# 2017_LEVI.net
KiCad netlist of a schematic drawn in Altium Designer
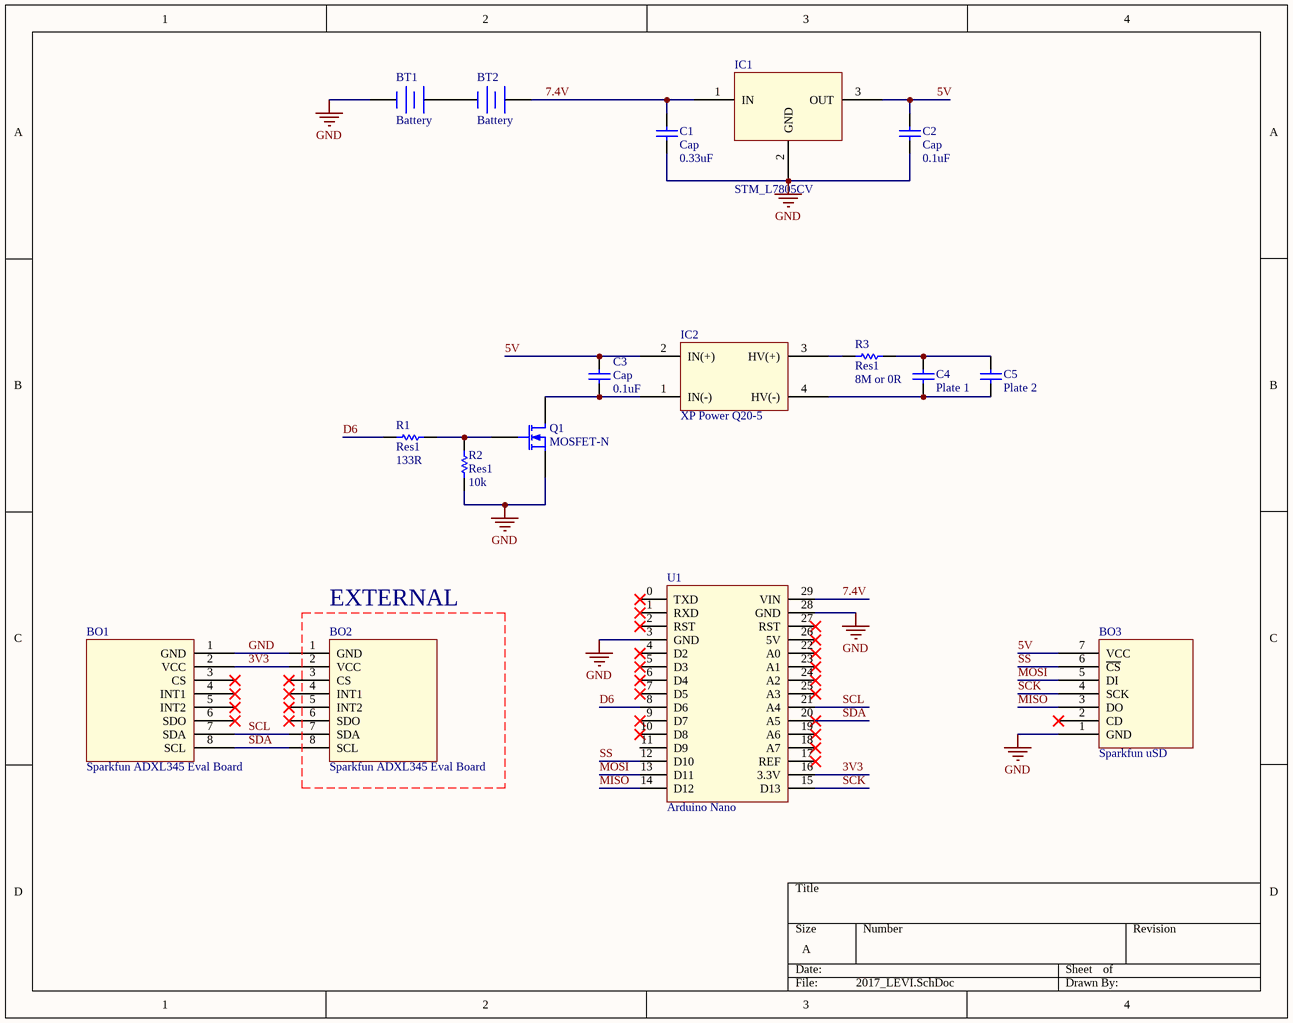
[diagram p0: 2017_LEVI.SchDoc]

(export (version "E")
  (design (tool "Eeschema 10.0.6"))
  (components
    (comp (ref "BO1")
      (value "Sparkfun ADXL345 Eval Board")
      (footprint "Sparkfun ADXL345 Breakout")
      (libsource (lib "") (part "Sparkfun ADXL345 Eval Board_1"))
    )
    (comp (ref "BO2")
      (value "Sparkfun ADXL345 Eval Board")
      (footprint "Sparkfun ADXL345 Breakout")
      (libsource (lib "2017_LEVI") (part "Sparkfun ADXL345 Eval Board"))
    )
    (comp (ref "BO3")
      (value "Sparkfun uSD")
      (footprint "Sparkfun MicroSD Breakout")
      (libsource (lib "2017_LEVI") (part "Sparkfun uSD"))
    )
    (comp (ref "BT1")
      (value "Battery")
      (footprint "BAT-2")
      (description "Multicell Battery")
      (fields (field (name "PUBLISHER") "Altium Limited"))
      (libsource (lib "Miscellaneous Devices") (part "Battery"))
    )
    (comp (ref "BT2")
      (value "Battery")
      (footprint "BAT-2")
      (description "Multicell Battery")
      (fields (field (name "PUBLISHER") "Altium Limited"))
      (libsource (lib "Miscellaneous Devices") (part "Battery"))
    )
    (comp (ref "C1")
      (value "Cap")
      (footprint "RAD-0.3")
      (description "Capacitor")
      (fields (field (name "ALTIUM_VALUE") "0.33uF") (field (name "PUBLISHER") "Altium Limited"))
      (libsource (lib "Miscellaneous Devices") (part "Cap"))
    )
    (comp (ref "C2")
      (value "Cap")
      (footprint "RAD-0.3")
      (description "Capacitor")
      (fields (field (name "ALTIUM_VALUE") "0.1uF") (field (name "PUBLISHER") "Altium Limited"))
      (libsource (lib "Miscellaneous Devices") (part "Cap"))
    )
    (comp (ref "C3")
      (value "Cap")
      (footprint "RAD-0.3")
      (description "Capacitor")
      (fields (field (name "ALTIUM_VALUE") "0.1uF") (field (name "PUBLISHER") "Altium Limited"))
      (libsource (lib "Miscellaneous Devices") (part "Cap"))
    )
    (comp (ref "C4")
      (value "Plate 1")
      (footprint "RAD-0.3")
      (description "Capacitor")
      (fields (field (name "PUBLISHER") "Altium Limited"))
      (libsource (lib "Miscellaneous Devices") (part "Cap"))
    )
    (comp (ref "C5")
      (value "Plate 2")
      (footprint "RAD-0.3")
      (description "Capacitor")
      (fields (field (name "PUBLISHER") "Altium Limited"))
      (libsource (lib "Miscellaneous Devices") (part "Cap"))
    )
    (comp (ref "IC1") (value "STM_L7805CV") (libsource (lib "2017_LEVI") (part "STM_L7805CV")))
    (comp (ref "IC2") (value "XP Power Q20-5") (libsource (lib "2017_LEVI") (part "XP Power Q20-5")))
    (comp (ref "Q1")
      (value "MOSFET-N")
      (footprint "E3")
      (description "N-Channel MOSFET")
      (fields (field (name "PUBLISHER") "Altium Limited"))
      (libsource (lib "Miscellaneous Devices") (part "MOSFET-N"))
    )
    (comp (ref "R1")
      (value "Res1")
      (footprint "AXIAL-0.3")
      (description "Resistor")
      (fields (field (name "ALTIUM_VALUE") "133R") (field (name "PUBLISHER") "Altium Limited"))
      (libsource (lib "Miscellaneous Devices") (part "Res1"))
    )
    (comp (ref "R2")
      (value "Res1")
      (footprint "AXIAL-0.3")
      (description "Resistor")
      (fields (field (name "ALTIUM_VALUE") "10k") (field (name "PUBLISHER") "Altium Limited"))
      (libsource (lib "Miscellaneous Devices") (part "Res1"))
    )
    (comp (ref "R3")
      (value "Res1")
      (footprint "AXIAL-0.3")
      (description "Resistor")
      (fields (field (name "ALTIUM_VALUE") "8M or 0R") (field (name "PUBLISHER") "Altium Limited"))
      (libsource (lib "Miscellaneous Devices") (part "Res1"))
    )
    (comp (ref "U1")
      (value "Arduino Nano")
      (footprint "Arduino Nano")
      (libsource (lib "2017_LEVI") (part "Arduino Nano"))
    )
  )
  (nets
    (net (code "1") (name "/3V3") (class "Default")
      (node (ref "BO1") (pin "2") (pinfunction "VCC_2") (pintype "passive"))
      (node (ref "BO2") (pin "2") (pinfunction "VCC_2") (pintype "passive"))
      (node (ref "U1") (pin "16") (pinfunction "3.3V_16") (pintype "passive"))
    )
    (net (code "2") (name "/5V") (class "Default")
      (node (ref "BO3") (pin "7") (pinfunction "VCC_7") (pintype "passive"))
      (node (ref "C2") (pin "2") (pinfunction "2_2") (pintype "passive"))
      (node (ref "C3") (pin "2") (pinfunction "2_2") (pintype "passive"))
      (node (ref "IC1") (pin "3") (pinfunction "OUT_3") (pintype "passive"))
      (node (ref "IC2") (pin "2") (pinfunction "IN(+)_2") (pintype "passive"))
    )
    (net (code "3") (name "/7.4V") (class "Default")
      (node (ref "BT2") (pin "1") (pinfunction "+_1") (pintype "passive"))
      (node (ref "C1") (pin "2") (pinfunction "2_2") (pintype "passive"))
      (node (ref "IC1") (pin "1") (pinfunction "IN_1") (pintype "passive"))
      (node (ref "U1") (pin "29") (pinfunction "VIN_29") (pintype "passive"))
    )
    (net (code "4") (name "/D6") (class "Default")
      (node (ref "R1") (pin "1") (pinfunction "1_1") (pintype "passive"))
      (node (ref "U1") (pin "8") (pinfunction "D6_8") (pintype "passive"))
    )
    (net (code "5") (name "/MISO") (class "Default")
      (node (ref "BO3") (pin "3") (pinfunction "DO_3") (pintype "passive"))
      (node (ref "U1") (pin "14") (pinfunction "D12_14") (pintype "passive"))
    )
    (net (code "6") (name "/MOSI") (class "Default")
      (node (ref "BO3") (pin "5") (pinfunction "DI_5") (pintype "passive"))
      (node (ref "U1") (pin "13") (pinfunction "D11_13") (pintype "passive"))
    )
    (net (code "7") (name "/SCK") (class "Default")
      (node (ref "BO3") (pin "4") (pinfunction "SCK_4") (pintype "passive"))
      (node (ref "U1") (pin "15") (pinfunction "D13_15") (pintype "passive"))
    )
    (net (code "8") (name "/SCL") (class "Default")
      (node (ref "BO1") (pin "7") (pinfunction "SDA_7") (pintype "passive"))
      (node (ref "BO2") (pin "7") (pinfunction "SDA_7") (pintype "passive"))
      (node (ref "U1") (pin "21") (pinfunction "A4_21") (pintype "passive"))
    )
    (net (code "9") (name "/SDA") (class "Default")
      (node (ref "BO1") (pin "8") (pinfunction "SCL_8") (pintype "passive"))
      (node (ref "BO2") (pin "8") (pinfunction "SCL_8") (pintype "passive"))
      (node (ref "U1") (pin "20") (pinfunction "A5_20") (pintype "passive"))
    )
    (net (code "10") (name "/SS") (class "Default")
      (node (ref "BO3") (pin "6") (pinfunction "~{CS}_6") (pintype "passive"))
      (node (ref "U1") (pin "12") (pinfunction "D10_12") (pintype "passive"))
    )
    (net (code "11") (name "GND") (class "Default")
      (node (ref "BO1") (pin "1") (pinfunction "GND_1") (pintype "passive"))
      (node (ref "BO2") (pin "1") (pinfunction "GND_1") (pintype "passive"))
      (node (ref "BO3") (pin "1") (pinfunction "GND_1") (pintype "passive"))
      (node (ref "BT1") (pin "2") (pinfunction "-_2") (pintype "passive"))
      (node (ref "C1") (pin "1") (pinfunction "1_1") (pintype "passive"))
      (node (ref "C2") (pin "1") (pinfunction "1_1") (pintype "passive"))
      (node (ref "IC1") (pin "2") (pinfunction "GND_2") (pintype "passive"))
      (node (ref "Q1") (pin "3") (pinfunction "S_3") (pintype "passive"))
      (node (ref "R2") (pin "1") (pinfunction "1_1") (pintype "passive"))
      (node (ref "U1") (pin "28") (pinfunction "GND_28") (pintype "passive"))
      (node (ref "U1") (pin "3") (pinfunction "GND_3") (pintype "passive"))
    )
    (net (code "12") (name "Net-(BT1-+)") (class "Default")
      (node (ref "BT1") (pin "1") (pinfunction "+_1") (pintype "passive"))
      (node (ref "BT2") (pin "2") (pinfunction "-_2") (pintype "passive"))
    )
    (net (code "13") (name "Net-(C4-Pad2)") (class "Default")
      (node (ref "C4") (pin "2") (pinfunction "2_2") (pintype "passive"))
      (node (ref "C5") (pin "2") (pinfunction "2_2") (pintype "passive"))
      (node (ref "R3") (pin "2") (pinfunction "2_2") (pintype "passive"))
    )
    (net (code "14") (name "Net-(IC2-HV(+))") (class "Default")
      (node (ref "IC2") (pin "3") (pinfunction "HV(+)_3") (pintype "passive"))
      (node (ref "R3") (pin "1") (pinfunction "1_1") (pintype "passive"))
    )
    (net (code "15") (name "Net-(IC2-HV(-))") (class "Default")
      (node (ref "C4") (pin "1") (pinfunction "1_1") (pintype "passive"))
      (node (ref "C5") (pin "1") (pinfunction "1_1") (pintype "passive"))
      (node (ref "IC2") (pin "4") (pinfunction "HV(-)_4") (pintype "passive"))
    )
    (net (code "16") (name "Net-(IC2-IN(-))") (class "Default")
      (node (ref "C3") (pin "1") (pinfunction "1_1") (pintype "passive"))
      (node (ref "IC2") (pin "1") (pinfunction "IN(-)_1") (pintype "passive"))
      (node (ref "Q1") (pin "2") (pinfunction "D_2") (pintype "passive"))
    )
    (net (code "17") (name "Net-(Q1-G)") (class "Default")
      (node (ref "Q1") (pin "1") (pinfunction "G_1") (pintype "passive"))
      (node (ref "R1") (pin "2") (pinfunction "2_2") (pintype "passive"))
      (node (ref "R2") (pin "2") (pinfunction "2_2") (pintype "passive"))
    )
    (net (code "18") (name "unconnected-(BO1-CS-Pad3)") (class "Default")
      (node (ref "BO1") (pin "3") (pinfunction "CS_3") (pintype "passive+no_connect"))
    )
    (net (code "19") (name "unconnected-(BO1-INT1-Pad4)") (class "Default")
      (node (ref "BO1") (pin "4") (pinfunction "INT1_4") (pintype "passive+no_connect"))
    )
    (net (code "20") (name "unconnected-(BO1-INT2-Pad5)") (class "Default")
      (node (ref "BO1") (pin "5") (pinfunction "INT2_5") (pintype "passive+no_connect"))
    )
    (net (code "21") (name "unconnected-(BO1-SDO-Pad6)") (class "Default")
      (node (ref "BO1") (pin "6") (pinfunction "SDO_6") (pintype "passive+no_connect"))
    )
    (net (code "22") (name "unconnected-(BO2-CS-Pad3)") (class "Default")
      (node (ref "BO2") (pin "3") (pinfunction "CS_3") (pintype "passive+no_connect"))
    )
    (net (code "23") (name "unconnected-(BO2-INT1-Pad4)") (class "Default")
      (node (ref "BO2") (pin "4") (pinfunction "INT1_4") (pintype "passive+no_connect"))
    )
    (net (code "24") (name "unconnected-(BO2-INT2-Pad5)") (class "Default")
      (node (ref "BO2") (pin "5") (pinfunction "INT2_5") (pintype "passive+no_connect"))
    )
    (net (code "25") (name "unconnected-(BO2-SDO-Pad6)") (class "Default")
      (node (ref "BO2") (pin "6") (pinfunction "SDO_6") (pintype "passive+no_connect"))
    )
    (net (code "26") (name "unconnected-(BO3-CD-Pad2)") (class "Default")
      (node (ref "BO3") (pin "2") (pinfunction "CD_2") (pintype "passive+no_connect"))
    )
    (net (code "27") (name "unconnected-(U1-5V-Pad26)") (class "Default")
      (node (ref "U1") (pin "26") (pinfunction "5V_26") (pintype "passive+no_connect"))
    )
    (net (code "28") (name "unconnected-(U1-A0-Pad22)") (class "Default")
      (node (ref "U1") (pin "22") (pinfunction "A0_22") (pintype "passive+no_connect"))
    )
    (net (code "29") (name "unconnected-(U1-A1-Pad23)") (class "Default")
      (node (ref "U1") (pin "23") (pinfunction "A1_23") (pintype "passive+no_connect"))
    )
    (net (code "30") (name "unconnected-(U1-A2-Pad24)") (class "Default")
      (node (ref "U1") (pin "24") (pinfunction "A2_24") (pintype "passive+no_connect"))
    )
    (net (code "31") (name "unconnected-(U1-A3-Pad25)") (class "Default")
      (node (ref "U1") (pin "25") (pinfunction "A3_25") (pintype "passive+no_connect"))
    )
    (net (code "32") (name "unconnected-(U1-A6-Pad19)") (class "Default")
      (node (ref "U1") (pin "19") (pinfunction "A6_19") (pintype "passive+no_connect"))
    )
    (net (code "33") (name "unconnected-(U1-A7-Pad18)") (class "Default")
      (node (ref "U1") (pin "18") (pinfunction "A7_18") (pintype "passive+no_connect"))
    )
    (net (code "34") (name "unconnected-(U1-D2-Pad4)") (class "Default")
      (node (ref "U1") (pin "4") (pinfunction "D2_4") (pintype "passive+no_connect"))
    )
    (net (code "35") (name "unconnected-(U1-D3-Pad5)") (class "Default")
      (node (ref "U1") (pin "5") (pinfunction "D3_5") (pintype "passive+no_connect"))
    )
    (net (code "36") (name "unconnected-(U1-D4-Pad6)") (class "Default")
      (node (ref "U1") (pin "6") (pinfunction "D4_6") (pintype "passive+no_connect"))
    )
    (net (code "37") (name "unconnected-(U1-D5-Pad7)") (class "Default")
      (node (ref "U1") (pin "7") (pinfunction "D5_7") (pintype "passive+no_connect"))
    )
    (net (code "38") (name "unconnected-(U1-D7-Pad9)") (class "Default")
      (node (ref "U1") (pin "9") (pinfunction "D7_9") (pintype "passive+no_connect"))
    )
    (net (code "39") (name "unconnected-(U1-D8-Pad10)") (class "Default")
      (node (ref "U1") (pin "10") (pinfunction "D8_10") (pintype "passive+no_connect"))
    )
    (net (code "40") (name "unconnected-(U1-D9-Pad11)") (class "Default")
      (node (ref "U1") (pin "11") (pinfunction "D9_11") (pintype "passive"))
    )
    (net (code "41") (name "unconnected-(U1-REF-Pad17)") (class "Default")
      (node (ref "U1") (pin "17") (pinfunction "REF_17") (pintype "passive+no_connect"))
    )
    (net (code "42") (name "unconnected-(U1-RST-Pad2)") (class "Default")
      (node (ref "U1") (pin "2") (pinfunction "RST_2") (pintype "passive+no_connect"))
    )
    (net (code "43") (name "unconnected-(U1-RST-Pad27)") (class "Default")
      (node (ref "U1") (pin "27") (pinfunction "RST_27") (pintype "passive+no_connect"))
    )
    (net (code "44") (name "unconnected-(U1-RXD-Pad1)") (class "Default")
      (node (ref "U1") (pin "1") (pinfunction "RXD_1") (pintype "passive+no_connect"))
    )
    (net (code "45") (name "unconnected-(U1-TXD-Pad0)") (class "Default")
      (node (ref "U1") (pin "0") (pinfunction "TXD_0") (pintype "passive+no_connect"))
    )
  )
)
